# U100.net
KiCad netlist of a schematic drawn in EasyEDA Pro
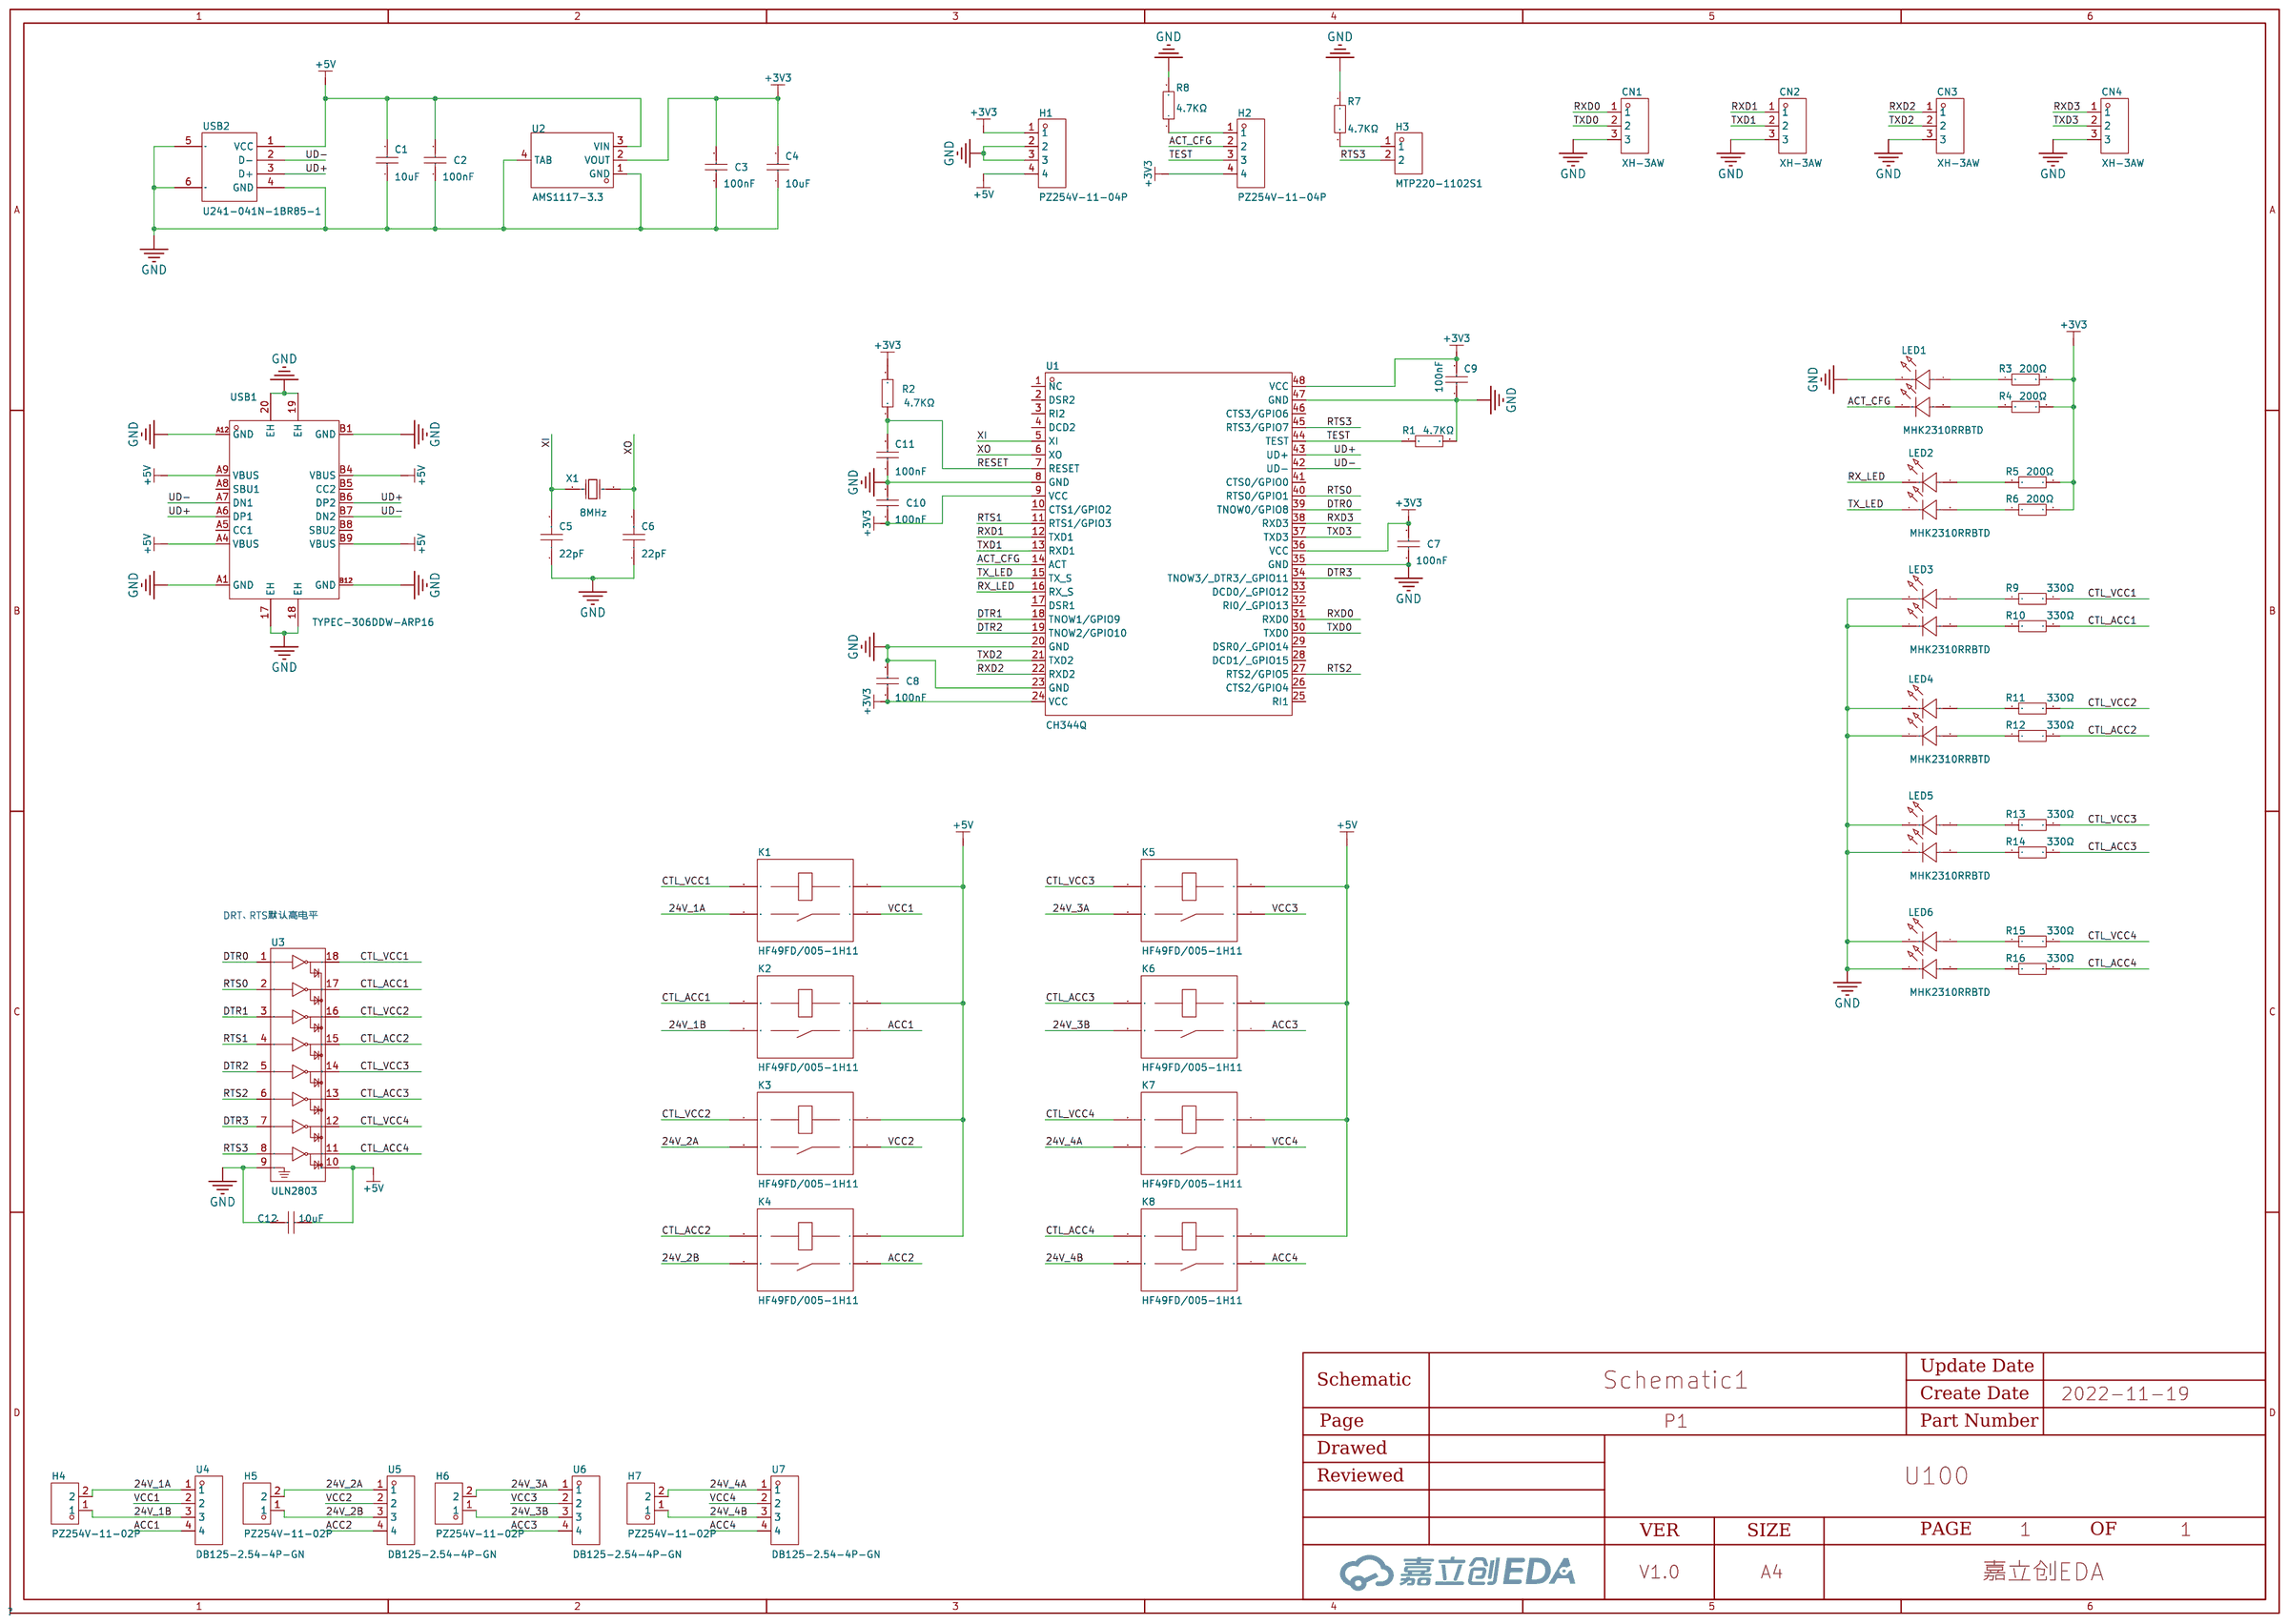
[diagram p0: schematic sheet]

(export (version "E")
  (design (tool "Eeschema 10.0.6"))
  (components
    (comp (ref "C1")
      (value "10uF")
      (footprint "easyedapro:C0805")
      (description "温度系数:X7R;容值:100nF;精度:±10%;额定电压:50V;")
      (fields (field (name "Manufacturer Part") "0805B104K500NT") (field (name "Manufacturer") "FH(风华)"))
      (libsource (lib "easyedapro") (part "0805B104K500NT"))
    )
    (comp (ref "C2")
      (value "100nF")
      (footprint "easyedapro:C0805")
      (description "温度系数:X7R;容值:100nF;精度:±10%;额定电压:50V;")
      (fields (field (name "Manufacturer Part") "0805B104K500NT") (field (name "Manufacturer") "FH(风华)"))
      (libsource (lib "easyedapro") (part "0805B104K500NT"))
    )
    (comp (ref "C3")
      (value "100nF")
      (footprint "easyedapro:C0805")
      (description "温度系数:X7R;容值:100nF;精度:±10%;额定电压:50V;")
      (fields (field (name "Manufacturer Part") "0805B104K500NT") (field (name "Manufacturer") "FH(风华)"))
      (libsource (lib "easyedapro") (part "0805B104K500NT"))
    )
    (comp (ref "C4")
      (value "10uF")
      (footprint "easyedapro:C0805")
      (description "温度系数:X7R;容值:100nF;精度:±10%;额定电压:50V;")
      (fields (field (name "Manufacturer Part") "0805B104K500NT") (field (name "Manufacturer") "FH(风华)"))
      (libsource (lib "easyedapro") (part "0805B104K500NT"))
    )
    (comp (ref "C5")
      (value "22pF")
      (footprint "easyedapro:C0805")
      (description "温度系数:C0G;精度:±5%;额定电压:50V;容值:22pF;")
      (fields (field (name "Manufacturer Part") "0805CG220J500NT") (field (name "Manufacturer") "FH(风华)"))
      (libsource (lib "easyedapro") (part "0805CG220J500NT_C24658"))
    )
    (comp (ref "C6")
      (value "22pF")
      (footprint "easyedapro:C0805")
      (description "温度系数:C0G;精度:±5%;额定电压:50V;容值:22pF;")
      (fields (field (name "Manufacturer Part") "0805CG220J500NT") (field (name "Manufacturer") "FH(风华)"))
      (libsource (lib "easyedapro") (part "0805CG220J500NT_C24658"))
    )
    (comp (ref "C7")
      (value "100nF")
      (footprint "easyedapro:C0805")
      (description "温度系数:X7R;容值:100nF;精度:±10%;额定电压:50V;")
      (fields (field (name "Manufacturer Part") "0805B104K500NT") (field (name "Manufacturer") "FH(风华)"))
      (libsource (lib "easyedapro") (part "0805B104K500NT"))
    )
    (comp (ref "C8")
      (value "100nF")
      (footprint "easyedapro:C0805")
      (description "温度系数:X7R;容值:100nF;精度:±10%;额定电压:50V;")
      (fields (field (name "Manufacturer Part") "0805B104K500NT") (field (name "Manufacturer") "FH(风华)"))
      (libsource (lib "easyedapro") (part "0805B104K500NT"))
    )
    (comp (ref "C9")
      (value "100nF")
      (footprint "easyedapro:C0805")
      (description "温度系数:X7R;容值:100nF;精度:±10%;额定电压:50V;")
      (fields (field (name "Manufacturer Part") "0805B104K500NT") (field (name "Manufacturer") "FH(风华)"))
      (libsource (lib "easyedapro") (part "0805B104K500NT"))
    )
    (comp (ref "C10")
      (value "100nF")
      (footprint "easyedapro:C0805")
      (description "温度系数:X7R;容值:100nF;精度:±10%;额定电压:50V;")
      (fields (field (name "Manufacturer Part") "0805B104K500NT") (field (name "Manufacturer") "FH(风华)"))
      (libsource (lib "easyedapro") (part "0805B104K500NT"))
    )
    (comp (ref "C11")
      (value "100nF")
      (footprint "easyedapro:C0805")
      (description "温度系数:X7R;容值:100nF;精度:±10%;额定电压:50V;")
      (fields (field (name "Manufacturer Part") "0805B104K500NT") (field (name "Manufacturer") "FH(风华)"))
      (libsource (lib "easyedapro") (part "0805B104K500NT"))
    )
    (comp (ref "C12")
      (value "10uF")
      (footprint "easyedapro:C0805")
      (description "温度系数:X7R;容值:100nF;精度:±10%;额定电压:50V;")
      (fields (field (name "Manufacturer Part") "0805B104K500NT") (field (name "Manufacturer") "FH(风华)"))
      (libsource (lib "easyedapro") (part "0805B104K500NT"))
    )
    (comp (ref "CN1")
      (value "XH-3AW")
      (footprint "easyedapro:CONN-TH_3P-P2.54_HCTL_XH-3AW")
      (description "参考系列:XH;间距:2.54mm;插针结构:1x3P;排数:1;每排PIN数:3;行距:-;公母:公型插针;安装方式:弯插;额定电流:3A;工作温度范围:-25°C~+85°C;")
      (fields (field (name "Manufacturer") "HCTL(华灿天禄)"))
      (libsource (lib "easyedapro") (part "XH-3AW_C2908612"))
    )
    (comp (ref "CN2")
      (value "XH-3AW")
      (footprint "easyedapro:CONN-TH_3P-P2.54_HCTL_XH-3AW")
      (description "参考系列:XH;间距:2.54mm;插针结构:1x3P;排数:1;每排PIN数:3;行距:-;公母:公型插针;安装方式:弯插;额定电流:3A;工作温度范围:-25°C~+85°C;")
      (fields (field (name "Manufacturer") "HCTL(华灿天禄)"))
      (libsource (lib "easyedapro") (part "XH-3AW_C2908612"))
    )
    (comp (ref "CN3")
      (value "XH-3AW")
      (footprint "easyedapro:CONN-TH_3P-P2.54_HCTL_XH-3AW")
      (description "参考系列:XH;间距:2.54mm;插针结构:1x3P;排数:1;每排PIN数:3;行距:-;公母:公型插针;安装方式:弯插;额定电流:3A;工作温度范围:-25°C~+85°C;")
      (fields (field (name "Manufacturer") "HCTL(华灿天禄)"))
      (libsource (lib "easyedapro") (part "XH-3AW_C2908612"))
    )
    (comp (ref "CN4")
      (value "XH-3AW")
      (footprint "easyedapro:CONN-TH_3P-P2.54_HCTL_XH-3AW")
      (description "参考系列:XH;间距:2.54mm;插针结构:1x3P;排数:1;每排PIN数:3;行距:-;公母:公型插针;安装方式:弯插;额定电流:3A;工作温度范围:-25°C~+85°C;")
      (fields (field (name "Manufacturer") "HCTL(华灿天禄)"))
      (libsource (lib "easyedapro") (part "XH-3AW_C2908612"))
    )
    (comp (ref "H1")
      (value "PZ254V-11-04P")
      (footprint "easyedapro:HDR-TH_4P-P2.54-V-M")
      (fields (field (name "Manufacturer") "XFCN(兴飞)"))
      (libsource (lib "easyedapro") (part "PZ254V-11-04P_C2691448"))
    )
    (comp (ref "H2")
      (value "PZ254V-11-04P")
      (footprint "easyedapro:HDR-TH_4P-P2.54-V-M")
      (fields (field (name "Manufacturer") "XFCN(兴飞)"))
      (libsource (lib "easyedapro") (part "PZ254V-11-04P_C2691448"))
    )
    (comp (ref "H3")
      (value "MTP220-1102S1")
      (footprint "easyedapro:HDR-TH_2P-P2.00-V-M")
      (fields (field (name "Manufacturer") "MINTRON(明硕)"))
      (libsource (lib "easyedapro") (part "MTP220-1102S1"))
    )
    (comp (ref "H4")
      (value "PZ254V-11-02P")
      (footprint "easyedapro:HDR-TH_2P-P2.54-V-M")
      (fields (field (name "Manufacturer") "XFCN(兴飞)"))
      (libsource (lib "easyedapro") (part "PZ254V-11-02P"))
    )
    (comp (ref "H5")
      (value "PZ254V-11-02P")
      (footprint "easyedapro:HDR-TH_2P-P2.54-V-M")
      (fields (field (name "Manufacturer") "XFCN(兴飞)"))
      (libsource (lib "easyedapro") (part "PZ254V-11-02P"))
    )
    (comp (ref "H6")
      (value "PZ254V-11-02P")
      (footprint "easyedapro:HDR-TH_2P-P2.54-V-M")
      (fields (field (name "Manufacturer") "XFCN(兴飞)"))
      (libsource (lib "easyedapro") (part "PZ254V-11-02P"))
    )
    (comp (ref "H7")
      (value "PZ254V-11-02P")
      (footprint "easyedapro:HDR-TH_2P-P2.54-V-M")
      (fields (field (name "Manufacturer") "XFCN(兴飞)"))
      (libsource (lib "easyedapro") (part "PZ254V-11-02P"))
    )
    (comp (ref "K1")
      (value "HF49FD/005-1H11")
      (footprint "easyedapro:RELAY-TH_HF49FD-XXX-1H11-XXX")
      (description "线圈电压:5V;线圈类型:非极化-单线圈;触点形式:一组常开:1A(单刀单掷-常开);最大切换电流:5A;")
      (fields (field (name "Manufacturer") "HF(宏发)"))
      (libsource (lib "easyedapro") (part "HF49FD/005-1H11"))
    )
    (comp (ref "K2")
      (value "HF49FD/005-1H11")
      (footprint "easyedapro:RELAY-TH_HF49FD-XXX-1H11-XXX")
      (description "线圈电压:5V;线圈类型:非极化-单线圈;触点形式:一组常开:1A(单刀单掷-常开);最大切换电流:5A;")
      (fields (field (name "Manufacturer") "HF(宏发)"))
      (libsource (lib "easyedapro") (part "HF49FD/005-1H11"))
    )
    (comp (ref "K3")
      (value "HF49FD/005-1H11")
      (footprint "easyedapro:RELAY-TH_HF49FD-XXX-1H11-XXX")
      (description "线圈电压:5V;线圈类型:非极化-单线圈;触点形式:一组常开:1A(单刀单掷-常开);最大切换电流:5A;")
      (fields (field (name "Manufacturer") "HF(宏发)"))
      (libsource (lib "easyedapro") (part "HF49FD/005-1H11"))
    )
    (comp (ref "K4")
      (value "HF49FD/005-1H11")
      (footprint "easyedapro:RELAY-TH_HF49FD-XXX-1H11-XXX")
      (description "线圈电压:5V;线圈类型:非极化-单线圈;触点形式:一组常开:1A(单刀单掷-常开);最大切换电流:5A;")
      (fields (field (name "Manufacturer") "HF(宏发)"))
      (libsource (lib "easyedapro") (part "HF49FD/005-1H11"))
    )
    (comp (ref "K5")
      (value "HF49FD/005-1H11")
      (footprint "easyedapro:RELAY-TH_HF49FD-XXX-1H11-XXX")
      (description "线圈电压:5V;线圈类型:非极化-单线圈;触点形式:一组常开:1A(单刀单掷-常开);最大切换电流:5A;")
      (fields (field (name "Manufacturer") "HF(宏发)"))
      (libsource (lib "easyedapro") (part "HF49FD/005-1H11"))
    )
    (comp (ref "K6")
      (value "HF49FD/005-1H11")
      (footprint "easyedapro:RELAY-TH_HF49FD-XXX-1H11-XXX")
      (description "线圈电压:5V;线圈类型:非极化-单线圈;触点形式:一组常开:1A(单刀单掷-常开);最大切换电流:5A;")
      (fields (field (name "Manufacturer") "HF(宏发)"))
      (libsource (lib "easyedapro") (part "HF49FD/005-1H11"))
    )
    (comp (ref "K7")
      (value "HF49FD/005-1H11")
      (footprint "easyedapro:RELAY-TH_HF49FD-XXX-1H11-XXX")
      (description "线圈电压:5V;线圈类型:非极化-单线圈;触点形式:一组常开:1A(单刀单掷-常开);最大切换电流:5A;")
      (fields (field (name "Manufacturer") "HF(宏发)"))
      (libsource (lib "easyedapro") (part "HF49FD/005-1H11"))
    )
    (comp (ref "K8")
      (value "HF49FD/005-1H11")
      (footprint "easyedapro:RELAY-TH_HF49FD-XXX-1H11-XXX")
      (description "线圈电压:5V;线圈类型:非极化-单线圈;触点形式:一组常开:1A(单刀单掷-常开);最大切换电流:5A;")
      (fields (field (name "Manufacturer") "HF(宏发)"))
      (libsource (lib "easyedapro") (part "HF49FD/005-1H11"))
    )
    (comp (ref "LED1")
      (value "MHK2310RRBTD")
      (footprint "easyedapro:LED-TH_4P-P2.54_MHK2310RRBTD")
      (description "发光颜色:红灯;二极管配置:-;透镜颜色:雾状红;主波长:700nm;峰值波长:-;色温:-;测试电流:20mA;功率:78mW;发光角度:80°;安装方式:-;工作温度:-25°C~+85°C;")
      (fields (field (name "Manufacturer") "MEIHUA(美华)"))
      (libsource (lib "easyedapro") (part "MHK2310RRBTD"))
    )
    (comp (ref "LED2")
      (value "MHK2310RRBTD")
      (footprint "easyedapro:LED-TH_4P-P2.54_MHK2310RRBTD")
      (description "发光颜色:红灯;二极管配置:-;透镜颜色:雾状红;主波长:700nm;峰值波长:-;色温:-;测试电流:20mA;功率:78mW;发光角度:80°;安装方式:-;工作温度:-25°C~+85°C;")
      (fields (field (name "Manufacturer") "MEIHUA(美华)"))
      (libsource (lib "easyedapro") (part "MHK2310RRBTD"))
    )
    (comp (ref "LED3")
      (value "MHK2310RRBTD")
      (footprint "easyedapro:LED-TH_4P-P2.54_MHK2310RRBTD")
      (description "发光颜色:红灯;二极管配置:-;透镜颜色:雾状红;主波长:700nm;峰值波长:-;色温:-;测试电流:20mA;功率:78mW;发光角度:80°;安装方式:-;工作温度:-25°C~+85°C;")
      (fields (field (name "Manufacturer") "MEIHUA(美华)"))
      (libsource (lib "easyedapro") (part "MHK2310RRBTD"))
    )
    (comp (ref "LED4")
      (value "MHK2310RRBTD")
      (footprint "easyedapro:LED-TH_4P-P2.54_MHK2310RRBTD")
      (description "发光颜色:红灯;二极管配置:-;透镜颜色:雾状红;主波长:700nm;峰值波长:-;色温:-;测试电流:20mA;功率:78mW;发光角度:80°;安装方式:-;工作温度:-25°C~+85°C;")
      (fields (field (name "Manufacturer") "MEIHUA(美华)"))
      (libsource (lib "easyedapro") (part "MHK2310RRBTD"))
    )
    (comp (ref "LED5")
      (value "MHK2310RRBTD")
      (footprint "easyedapro:LED-TH_4P-P2.54_MHK2310RRBTD")
      (description "发光颜色:红灯;二极管配置:-;透镜颜色:雾状红;主波长:700nm;峰值波长:-;色温:-;测试电流:20mA;功率:78mW;发光角度:80°;安装方式:-;工作温度:-25°C~+85°C;")
      (fields (field (name "Manufacturer") "MEIHUA(美华)"))
      (libsource (lib "easyedapro") (part "MHK2310RRBTD"))
    )
    (comp (ref "LED6")
      (value "MHK2310RRBTD")
      (footprint "easyedapro:LED-TH_4P-P2.54_MHK2310RRBTD")
      (description "发光颜色:红灯;二极管配置:-;透镜颜色:雾状红;主波长:700nm;峰值波长:-;色温:-;测试电流:20mA;功率:78mW;发光角度:80°;安装方式:-;工作温度:-25°C~+85°C;")
      (fields (field (name "Manufacturer") "MEIHUA(美华)"))
      (libsource (lib "easyedapro") (part "MHK2310RRBTD"))
    )
    (comp (ref "R1")
      (value "4.7KΩ")
      (footprint "easyedapro:R0805")
      (description "精度:±1%;温度系数:±800ppm/°C;阻值:0Ω;功率:0.125W;")
      (fields
        (field (name "Manufacturer Part") "0805W8F0000T5E")
        (field (name "Manufacturer") "UNI-ROYAL(厚声)")
      )
      (libsource (lib "easyedapro") (part "0805W8F0000T5E"))
    )
    (comp (ref "R2")
      (value "4.7KΩ")
      (footprint "easyedapro:R0805")
      (description "精度:±1%;温度系数:±800ppm/℃;阻值:0Ω;功率:0.125W;")
      (fields
        (field (name "Manufacturer Part") "0805W8F0000T5E")
        (field (name "Manufacturer") "UNI-ROYAL(厚声)")
      )
      (libsource (lib "easyedapro") (part "0805W8F0000T5E"))
    )
    (comp (ref "R3")
      (value "200Ω")
      (footprint "easyedapro:R0805")
      (description "精度:±1%;温度系数:±800ppm/°C;阻值:0Ω;功率:0.125W;")
      (fields
        (field (name "Manufacturer Part") "0805W8F0000T5E")
        (field (name "Manufacturer") "UNI-ROYAL(厚声)")
      )
      (libsource (lib "easyedapro") (part "0805W8F0000T5E"))
    )
    (comp (ref "R4")
      (value "200Ω")
      (footprint "easyedapro:R0805")
      (description "精度:±1%;温度系数:±800ppm/°C;阻值:0Ω;功率:0.125W;")
      (fields
        (field (name "Manufacturer Part") "0805W8F0000T5E")
        (field (name "Manufacturer") "UNI-ROYAL(厚声)")
      )
      (libsource (lib "easyedapro") (part "0805W8F0000T5E"))
    )
    (comp (ref "R5")
      (value "200Ω")
      (footprint "easyedapro:R0805")
      (description "精度:±1%;温度系数:±800ppm/°C;阻值:0Ω;功率:0.125W;")
      (fields
        (field (name "Manufacturer Part") "0805W8F0000T5E")
        (field (name "Manufacturer") "UNI-ROYAL(厚声)")
      )
      (libsource (lib "easyedapro") (part "0805W8F0000T5E"))
    )
    (comp (ref "R6")
      (value "200Ω")
      (footprint "easyedapro:R0805")
      (description "精度:±1%;温度系数:±800ppm/°C;阻值:0Ω;功率:0.125W;")
      (fields
        (field (name "Manufacturer Part") "0805W8F0000T5E")
        (field (name "Manufacturer") "UNI-ROYAL(厚声)")
      )
      (libsource (lib "easyedapro") (part "0805W8F0000T5E"))
    )
    (comp (ref "R7")
      (value "4.7KΩ")
      (footprint "easyedapro:R0805")
      (description "精度:±1%;温度系数:±800ppm/℃;阻值:0Ω;功率:0.125W;")
      (fields
        (field (name "Manufacturer Part") "0805W8F0000T5E")
        (field (name "Manufacturer") "UNI-ROYAL(厚声)")
      )
      (libsource (lib "easyedapro") (part "0805W8F0000T5E"))
    )
    (comp (ref "R8")
      (value "4.7KΩ")
      (footprint "easyedapro:R0805")
      (description "精度:±1%;温度系数:±800ppm/℃;阻值:0Ω;功率:0.125W;")
      (fields
        (field (name "Manufacturer Part") "0805W8F0000T5E")
        (field (name "Manufacturer") "UNI-ROYAL(厚声)")
      )
      (libsource (lib "easyedapro") (part "0805W8F0000T5E"))
    )
    (comp (ref "R9")
      (value "330Ω")
      (footprint "easyedapro:R0805")
      (description "精度:±1%;温度系数:±800ppm/°C;阻值:0Ω;功率:0.125W;")
      (fields
        (field (name "Manufacturer Part") "0805W8F0000T5E")
        (field (name "Manufacturer") "UNI-ROYAL(厚声)")
      )
      (libsource (lib "easyedapro") (part "0805W8F0000T5E"))
    )
    (comp (ref "R10")
      (value "330Ω")
      (footprint "easyedapro:R0805")
      (description "精度:±1%;温度系数:±800ppm/°C;阻值:0Ω;功率:0.125W;")
      (fields
        (field (name "Manufacturer Part") "0805W8F0000T5E")
        (field (name "Manufacturer") "UNI-ROYAL(厚声)")
      )
      (libsource (lib "easyedapro") (part "0805W8F0000T5E"))
    )
    (comp (ref "R11")
      (value "330Ω")
      (footprint "easyedapro:R0805")
      (description "精度:±1%;温度系数:±800ppm/°C;阻值:0Ω;功率:0.125W;")
      (fields
        (field (name "Manufacturer Part") "0805W8F0000T5E")
        (field (name "Manufacturer") "UNI-ROYAL(厚声)")
      )
      (libsource (lib "easyedapro") (part "0805W8F0000T5E"))
    )
    (comp (ref "R12")
      (value "330Ω")
      (footprint "easyedapro:R0805")
      (description "精度:±1%;温度系数:±800ppm/°C;阻值:0Ω;功率:0.125W;")
      (fields
        (field (name "Manufacturer Part") "0805W8F0000T5E")
        (field (name "Manufacturer") "UNI-ROYAL(厚声)")
      )
      (libsource (lib "easyedapro") (part "0805W8F0000T5E"))
    )
    (comp (ref "R13")
      (value "330Ω")
      (footprint "easyedapro:R0805")
      (description "精度:±1%;温度系数:±800ppm/°C;阻值:0Ω;功率:0.125W;")
      (fields
        (field (name "Manufacturer Part") "0805W8F0000T5E")
        (field (name "Manufacturer") "UNI-ROYAL(厚声)")
      )
      (libsource (lib "easyedapro") (part "0805W8F0000T5E"))
    )
    (comp (ref "R14")
      (value "330Ω")
      (footprint "easyedapro:R0805")
      (description "精度:±1%;温度系数:±800ppm/°C;阻值:0Ω;功率:0.125W;")
      (fields
        (field (name "Manufacturer Part") "0805W8F0000T5E")
        (field (name "Manufacturer") "UNI-ROYAL(厚声)")
      )
      (libsource (lib "easyedapro") (part "0805W8F0000T5E"))
    )
    (comp (ref "R15")
      (value "330Ω")
      (footprint "easyedapro:R0805")
      (description "精度:±1%;温度系数:±800ppm/°C;阻值:0Ω;功率:0.125W;")
      (fields
        (field (name "Manufacturer Part") "0805W8F0000T5E")
        (field (name "Manufacturer") "UNI-ROYAL(厚声)")
      )
      (libsource (lib "easyedapro") (part "0805W8F0000T5E"))
    )
    (comp (ref "R16")
      (value "330Ω")
      (footprint "easyedapro:R0805")
      (description "精度:±1%;温度系数:±800ppm/°C;阻值:0Ω;功率:0.125W;")
      (fields
        (field (name "Manufacturer Part") "0805W8F0000T5E")
        (field (name "Manufacturer") "UNI-ROYAL(厚声)")
      )
      (libsource (lib "easyedapro") (part "0805W8F0000T5E"))
    )
    (comp (ref "U1")
      (value "CH344Q")
      (footprint "easyedapro:LQFP-48_L7.0-W7.0-P0.50-LS9.0-BL")
      (description "USB转四路异步串口,波特率支持高达230400bps,提供4路RS485方向控制引脚,12GPIO等信号")
      (fields (field (name "Manufacturer") "WCH(南京沁恒)"))
      (libsource (lib "easyedapro") (part "CH344Q_C2988084"))
    )
    (comp (ref "U2")
      (value "AMS1117-3.3")
      (footprint "easyedapro:SOT-223-3_L6.5-W3.4-P2.30-LS7.0-BR")
      (description "输出类型:固定;输出极性:正;输出通道数:1;最大输入电压:18V;输出电压:3.3V;压差:1.4V@(1A);输出电流:800mA;电源纹波抑制比(PRSS):-;")
      (fields (field (name "Manufacturer") "PUOLOP(迪浦)"))
      (libsource (lib "easyedapro") (part "AMS1117-3.3_C351784"))
    )
    (comp (ref "U3")
      (value "ULN2803")
      (footprint "easyedapro:SOP-18_L11.5-W7.5-P1.27-LS10.3-BL")
      (fields (field (name "Manufacturer") "Gcore(扬州国芯)"))
      (libsource (lib "easyedapro") (part "ULN2803"))
    )
    (comp (ref "U4")
      (value "DB125-2.54-4P-GN")
      (footprint "easyedapro:CONN-TH_DB125-2.54-4P-GN")
      (fields (field (name "Manufacturer") "DIBO(地博电气)"))
      (libsource (lib "easyedapro") (part "DB125-2.54-4P-GN"))
    )
    (comp (ref "U5")
      (value "DB125-2.54-4P-GN")
      (footprint "easyedapro:CONN-TH_DB125-2.54-4P-GN")
      (fields (field (name "Manufacturer") "DIBO(地博电气)"))
      (libsource (lib "easyedapro") (part "DB125-2.54-4P-GN"))
    )
    (comp (ref "U6")
      (value "DB125-2.54-4P-GN")
      (footprint "easyedapro:CONN-TH_DB125-2.54-4P-GN")
      (fields (field (name "Manufacturer") "DIBO(地博电气)"))
      (libsource (lib "easyedapro") (part "DB125-2.54-4P-GN"))
    )
    (comp (ref "U7")
      (value "DB125-2.54-4P-GN")
      (footprint "easyedapro:CONN-TH_DB125-2.54-4P-GN")
      (fields (field (name "Manufacturer") "DIBO(地博电气)"))
      (libsource (lib "easyedapro") (part "DB125-2.54-4P-GN"))
    )
    (comp (ref "USB1")
      (value "TYPEC-306DDW-ARP16")
      (footprint "easyedapro:USB-C-TH_TYPEC-306DDW-ARP16")
      (fields (field (name "Manufacturer") "XUNPU(讯普)"))
      (libsource (lib "easyedapro") (part "TYPEC-306DDW-ARP16"))
    )
    (comp (ref "USB2")
      (value "U241-041N-1BR85-1")
      (footprint "easyedapro:USB-B-TH_U241-041N-1BR85-1")
      (fields (field (name "Manufacturer") "XKB Connectivity(中国星坤)"))
      (libsource (lib "easyedapro") (part "U241-041N-1BR85-1"))
    )
    (comp (ref "X1")
      (value "8MHz")
      (footprint "easyedapro:OSC-TH_L10.0-W4.5-P5.00")
      (description "晶振类型:49S晶振;频率:8MHz;频率公差:±20ppm;频率稳定度:±30ppm;负载电容:20pF;工作温度:-20℃~+70℃;")
      (fields (field (name "Manufacturer Part") "X49SD8MSD2SC") (field (name "Manufacturer") "YXC(扬兴晶振)"))
      (libsource (lib "easyedapro") (part "X49SD8MSD2SC"))
    )
  )
  (nets
    (net (code "1") (name "+3V3") (class "Default")
      (node (ref "C10") (pin "1") (pinfunction "1_1") (pintype "input"))
      (node (ref "C3") (pin "2") (pinfunction "2_2") (pintype "input"))
      (node (ref "C4") (pin "2") (pinfunction "2_2") (pintype "input"))
      (node (ref "C7") (pin "2") (pinfunction "2_2") (pintype "input"))
      (node (ref "C8") (pin "1") (pinfunction "1_1") (pintype "input"))
      (node (ref "C9") (pin "2") (pinfunction "2_2") (pintype "input"))
      (node (ref "H1") (pin "1") (pinfunction "1_1") (pintype "input"))
      (node (ref "H2") (pin "4") (pinfunction "4_4") (pintype "input"))
      (node (ref "R2") (pin "2") (pinfunction "2_2") (pintype "input"))
      (node (ref "R3") (pin "2") (pinfunction "2_2") (pintype "input"))
      (node (ref "R4") (pin "2") (pinfunction "2_2") (pintype "input"))
      (node (ref "R5") (pin "2") (pinfunction "2_2") (pintype "input"))
      (node (ref "R6") (pin "2") (pinfunction "2_2") (pintype "input"))
      (node (ref "U1") (pin "24") (pinfunction "VCC_24") (pintype "input"))
      (node (ref "U1") (pin "36") (pinfunction "VCC_36") (pintype "input"))
      (node (ref "U1") (pin "48") (pinfunction "VCC_48") (pintype "input"))
      (node (ref "U1") (pin "9") (pinfunction "VCC_9") (pintype "input"))
      (node (ref "U2") (pin "2") (pinfunction "VOUT_2") (pintype "input"))
    )
    (net (code "2") (name "+5V") (class "Default")
      (node (ref "C1") (pin "2") (pinfunction "2_2") (pintype "input"))
      (node (ref "C12") (pin "1") (pinfunction "1_1") (pintype "input"))
      (node (ref "C2") (pin "2") (pinfunction "2_2") (pintype "input"))
      (node (ref "H1") (pin "4") (pinfunction "4_4") (pintype "input"))
      (node (ref "K1") (pin "1") (pinfunction "1_1") (pintype "input"))
      (node (ref "K2") (pin "1") (pinfunction "1_1") (pintype "input"))
      (node (ref "K3") (pin "1") (pinfunction "1_1") (pintype "input"))
      (node (ref "K4") (pin "1") (pinfunction "1_1") (pintype "input"))
      (node (ref "K5") (pin "1") (pinfunction "1_1") (pintype "input"))
      (node (ref "K6") (pin "1") (pinfunction "1_1") (pintype "input"))
      (node (ref "K7") (pin "1") (pinfunction "1_1") (pintype "input"))
      (node (ref "K8") (pin "1") (pinfunction "1_1") (pintype "input"))
      (node (ref "U2") (pin "3") (pinfunction "VIN_3") (pintype "input"))
      (node (ref "U3") (pin "10") (pinfunction "COMMON_10") (pintype "input"))
      (node (ref "USB1") (pin "A4") (pinfunction "VBUS_A4") (pintype "input"))
      (node (ref "USB1") (pin "A9") (pinfunction "VBUS_A9") (pintype "input"))
      (node (ref "USB1") (pin "B4") (pinfunction "VBUS_B4") (pintype "input"))
      (node (ref "USB1") (pin "B9") (pinfunction "VBUS_B9") (pintype "input"))
      (node (ref "USB2") (pin "1") (pinfunction "VCC_1") (pintype "input"))
    )
    (net (code "3") (name "/24V_1A") (class "Default")
      (node (ref "H4") (pin "2") (pinfunction "2_2") (pintype "input"))
      (node (ref "K1") (pin "3") (pinfunction "3_3") (pintype "input"))
      (node (ref "U4") (pin "1") (pinfunction "1_1") (pintype "input"))
    )
    (net (code "4") (name "/24V_1B") (class "Default")
      (node (ref "H4") (pin "1") (pinfunction "1_1") (pintype "input"))
      (node (ref "K2") (pin "3") (pinfunction "3_3") (pintype "input"))
      (node (ref "U4") (pin "3") (pinfunction "3_3") (pintype "input"))
    )
    (net (code "5") (name "/24V_2A") (class "Default")
      (node (ref "H5") (pin "2") (pinfunction "2_2") (pintype "input"))
      (node (ref "K3") (pin "3") (pinfunction "3_3") (pintype "input"))
      (node (ref "U5") (pin "1") (pinfunction "1_1") (pintype "input"))
    )
    (net (code "6") (name "/24V_2B") (class "Default")
      (node (ref "H5") (pin "1") (pinfunction "1_1") (pintype "input"))
      (node (ref "K4") (pin "3") (pinfunction "3_3") (pintype "input"))
      (node (ref "U5") (pin "3") (pinfunction "3_3") (pintype "input"))
    )
    (net (code "7") (name "/24V_3A") (class "Default")
      (node (ref "H6") (pin "2") (pinfunction "2_2") (pintype "input"))
      (node (ref "K5") (pin "3") (pinfunction "3_3") (pintype "input"))
      (node (ref "U6") (pin "1") (pinfunction "1_1") (pintype "input"))
    )
    (net (code "8") (name "/24V_3B") (class "Default")
      (node (ref "H6") (pin "1") (pinfunction "1_1") (pintype "input"))
      (node (ref "K6") (pin "3") (pinfunction "3_3") (pintype "input"))
      (node (ref "U6") (pin "3") (pinfunction "3_3") (pintype "input"))
    )
    (net (code "9") (name "/24V_4A") (class "Default")
      (node (ref "H7") (pin "2") (pinfunction "2_2") (pintype "input"))
      (node (ref "K7") (pin "3") (pinfunction "3_3") (pintype "input"))
      (node (ref "U7") (pin "1") (pinfunction "1_1") (pintype "input"))
    )
    (net (code "10") (name "/24V_4B") (class "Default")
      (node (ref "H7") (pin "1") (pinfunction "1_1") (pintype "input"))
      (node (ref "K8") (pin "3") (pinfunction "3_3") (pintype "input"))
      (node (ref "U7") (pin "3") (pinfunction "3_3") (pintype "input"))
    )
    (net (code "11") (name "/ACC1") (class "Default")
      (node (ref "K2") (pin "4") (pinfunction "4_4") (pintype "input"))
      (node (ref "U4") (pin "4") (pinfunction "4_4") (pintype "input"))
    )
    (net (code "12") (name "/ACC2") (class "Default")
      (node (ref "K4") (pin "4") (pinfunction "4_4") (pintype "input"))
      (node (ref "U5") (pin "4") (pinfunction "4_4") (pintype "input"))
    )
    (net (code "13") (name "/ACC3") (class "Default")
      (node (ref "K6") (pin "4") (pinfunction "4_4") (pintype "input"))
      (node (ref "U6") (pin "4") (pinfunction "4_4") (pintype "input"))
    )
    (net (code "14") (name "/ACC4") (class "Default")
      (node (ref "K8") (pin "4") (pinfunction "4_4") (pintype "input"))
      (node (ref "U7") (pin "4") (pinfunction "4_4") (pintype "input"))
    )
    (net (code "15") (name "/ACT_CFG") (class "Default")
      (node (ref "H2") (pin "2") (pinfunction "2_2") (pintype "input"))
      (node (ref "LED1") (pin "1") (pinfunction "K_1") (pintype "input"))
      (node (ref "U1") (pin "14") (pinfunction "ACT_14") (pintype "input"))
    )
    (net (code "16") (name "/CTL_ACC1") (class "Default")
      (node (ref "K2") (pin "2") (pinfunction "2_2") (pintype "input"))
      (node (ref "R10") (pin "2") (pinfunction "2_2") (pintype "input"))
      (node (ref "U3") (pin "17") (pinfunction "O2_17") (pintype "input"))
    )
    (net (code "17") (name "/CTL_ACC2") (class "Default")
      (node (ref "K4") (pin "2") (pinfunction "2_2") (pintype "input"))
      (node (ref "R12") (pin "2") (pinfunction "2_2") (pintype "input"))
      (node (ref "U3") (pin "15") (pinfunction "O4_15") (pintype "input"))
    )
    (net (code "18") (name "/CTL_ACC3") (class "Default")
      (node (ref "K6") (pin "2") (pinfunction "2_2") (pintype "input"))
      (node (ref "R14") (pin "2") (pinfunction "2_2") (pintype "input"))
      (node (ref "U3") (pin "13") (pinfunction "O6_13") (pintype "input"))
    )
    (net (code "19") (name "/CTL_ACC4") (class "Default")
      (node (ref "K8") (pin "2") (pinfunction "2_2") (pintype "input"))
      (node (ref "R16") (pin "2") (pinfunction "2_2") (pintype "input"))
      (node (ref "U3") (pin "11") (pinfunction "O8_11") (pintype "input"))
    )
    (net (code "20") (name "/CTL_VCC1") (class "Default")
      (node (ref "K1") (pin "2") (pinfunction "2_2") (pintype "input"))
      (node (ref "R9") (pin "2") (pinfunction "2_2") (pintype "input"))
      (node (ref "U3") (pin "18") (pinfunction "O1_18") (pintype "input"))
    )
    (net (code "21") (name "/CTL_VCC2") (class "Default")
      (node (ref "K3") (pin "2") (pinfunction "2_2") (pintype "input"))
      (node (ref "R11") (pin "2") (pinfunction "2_2") (pintype "input"))
      (node (ref "U3") (pin "16") (pinfunction "O3_16") (pintype "input"))
    )
    (net (code "22") (name "/CTL_VCC3") (class "Default")
      (node (ref "K5") (pin "2") (pinfunction "2_2") (pintype "input"))
      (node (ref "R13") (pin "2") (pinfunction "2_2") (pintype "input"))
      (node (ref "U3") (pin "14") (pinfunction "O5_14") (pintype "input"))
    )
    (net (code "23") (name "/CTL_VCC4") (class "Default")
      (node (ref "K7") (pin "2") (pinfunction "2_2") (pintype "input"))
      (node (ref "R15") (pin "2") (pinfunction "2_2") (pintype "input"))
      (node (ref "U3") (pin "12") (pinfunction "O7_12") (pintype "input"))
    )
    (net (code "24") (name "/DTR0") (class "Default")
      (node (ref "U1") (pin "39") (pinfunction "TNOW0/GPIO8_39") (pintype "input"))
      (node (ref "U3") (pin "1") (pinfunction "I1_1") (pintype "input"))
    )
    (net (code "25") (name "/DTR1") (class "Default")
      (node (ref "U1") (pin "18") (pinfunction "TNOW1/GPIO9_18") (pintype "input"))
      (node (ref "U3") (pin "3") (pinfunction "I3_3") (pintype "input"))
    )
    (net (code "26") (name "/DTR2") (class "Default")
      (node (ref "U1") (pin "19") (pinfunction "TNOW2/GPIO10_19") (pintype "input"))
      (node (ref "U3") (pin "5") (pinfunction "I5_5") (pintype "input"))
    )
    (net (code "27") (name "/DTR3") (class "Default")
      (node (ref "U1") (pin "34") (pinfunction "TNOW3/_DTR3/_GPIO11_34") (pintype "input"))
      (node (ref "U3") (pin "7") (pinfunction "I7_7") (pintype "input"))
    )
    (net (code "28") (name "/RESET") (class "Default")
      (node (ref "C11") (pin "2") (pinfunction "2_2") (pintype "input"))
      (node (ref "R2") (pin "1") (pinfunction "1_1") (pintype "input"))
      (node (ref "U1") (pin "7") (pinfunction "RESET_7") (pintype "input"))
    )
    (net (code "29") (name "/RTS0") (class "Default")
      (node (ref "U1") (pin "40") (pinfunction "RTS0/GPIO1_40") (pintype "input"))
      (node (ref "U3") (pin "2") (pinfunction "I2_2") (pintype "input"))
    )
    (net (code "30") (name "/RTS1") (class "Default")
      (node (ref "U1") (pin "11") (pinfunction "RTS1/GPIO3_11") (pintype "input"))
      (node (ref "U3") (pin "4") (pinfunction "I4_4") (pintype "input"))
    )
    (net (code "31") (name "/RTS2") (class "Default")
      (node (ref "U1") (pin "27") (pinfunction "RTS2/GPIO5_27") (pintype "input"))
      (node (ref "U3") (pin "6") (pinfunction "I6_6") (pintype "input"))
    )
    (net (code "32") (name "/RTS3") (class "Default")
      (node (ref "H3") (pin "2") (pinfunction "2_2") (pintype "input"))
      (node (ref "U1") (pin "45") (pinfunction "RTS3/GPIO7_45") (pintype "input"))
      (node (ref "U3") (pin "8") (pinfunction "I8_8") (pintype "input"))
    )
    (net (code "33") (name "/RXD0") (class "Default")
      (node (ref "CN1") (pin "1") (pinfunction "1_1") (pintype "input"))
      (node (ref "U1") (pin "31") (pinfunction "RXD0_31") (pintype "input"))
    )
    (net (code "34") (name "/RXD1") (class "Default")
      (node (ref "CN2") (pin "1") (pinfunction "1_1") (pintype "input"))
      (node (ref "U1") (pin "12") (pinfunction "TXD1_12") (pintype "input"))
    )
    (net (code "35") (name "/RXD2") (class "Default")
      (node (ref "CN3") (pin "1") (pinfunction "1_1") (pintype "input"))
      (node (ref "U1") (pin "22") (pinfunction "RXD2_22") (pintype "input"))
    )
    (net (code "36") (name "/RXD3") (class "Default")
      (node (ref "CN4") (pin "1") (pinfunction "1_1") (pintype "input"))
      (node (ref "U1") (pin "38") (pinfunction "RXD3_38") (pintype "input"))
    )
    (net (code "37") (name "/RX_LED") (class "Default")
      (node (ref "LED2") (pin "3") (pinfunction "K_3") (pintype "input"))
      (node (ref "U1") (pin "16") (pinfunction "RX_S_16") (pintype "input"))
    )
    (net (code "38") (name "/TEST") (class "Default")
      (node (ref "H2") (pin "3") (pinfunction "3_3") (pintype "input"))
      (node (ref "R1") (pin "1") (pinfunction "1_1") (pintype "input"))
      (node (ref "U1") (pin "44") (pinfunction "TEST_44") (pintype "input"))
    )
    (net (code "39") (name "/TXD0") (class "Default")
      (node (ref "CN1") (pin "2") (pinfunction "2_2") (pintype "input"))
      (node (ref "U1") (pin "30") (pinfunction "TXD0_30") (pintype "input"))
    )
    (net (code "40") (name "/TXD1") (class "Default")
      (node (ref "CN2") (pin "2") (pinfunction "2_2") (pintype "input"))
      (node (ref "U1") (pin "13") (pinfunction "RXD1_13") (pintype "input"))
    )
    (net (code "41") (name "/TXD2") (class "Default")
      (node (ref "CN3") (pin "2") (pinfunction "2_2") (pintype "input"))
      (node (ref "U1") (pin "21") (pinfunction "TXD2_21") (pintype "input"))
    )
    (net (code "42") (name "/TXD3") (class "Default")
      (node (ref "CN4") (pin "2") (pinfunction "2_2") (pintype "input"))
      (node (ref "U1") (pin "37") (pinfunction "TXD3_37") (pintype "input"))
    )
    (net (code "43") (name "/TX_LED") (class "Default")
      (node (ref "LED2") (pin "1") (pinfunction "K_1") (pintype "input"))
      (node (ref "U1") (pin "15") (pinfunction "TX_S_15") (pintype "input"))
    )
    (net (code "44") (name "/UD+") (class "Default")
      (node (ref "U1") (pin "43") (pinfunction "UD+_43") (pintype "input"))
      (node (ref "USB1") (pin "A6") (pinfunction "DP1_A6") (pintype "input"))
      (node (ref "USB1") (pin "B6") (pinfunction "DP2_B6") (pintype "input"))
      (node (ref "USB2") (pin "3") (pinfunction "D+_3") (pintype "input"))
    )
    (net (code "45") (name "/UD-") (class "Default")
      (node (ref "U1") (pin "42") (pinfunction "UD-_42") (pintype "input"))
      (node (ref "USB1") (pin "A7") (pinfunction "DN1_A7") (pintype "input"))
      (node (ref "USB1") (pin "B7") (pinfunction "DN2_B7") (pintype "input"))
      (node (ref "USB2") (pin "2") (pinfunction "D-_2") (pintype "input"))
    )
    (net (code "46") (name "/VCC1") (class "Default")
      (node (ref "K1") (pin "4") (pinfunction "4_4") (pintype "input"))
      (node (ref "U4") (pin "2") (pinfunction "2_2") (pintype "input"))
    )
    (net (code "47") (name "/VCC2") (class "Default")
      (node (ref "K3") (pin "4") (pinfunction "4_4") (pintype "input"))
      (node (ref "U5") (pin "2") (pinfunction "2_2") (pintype "input"))
    )
    (net (code "48") (name "/VCC3") (class "Default")
      (node (ref "K5") (pin "4") (pinfunction "4_4") (pintype "input"))
      (node (ref "U6") (pin "2") (pinfunction "2_2") (pintype "input"))
    )
    (net (code "49") (name "/VCC4") (class "Default")
      (node (ref "K7") (pin "4") (pinfunction "4_4") (pintype "input"))
      (node (ref "U7") (pin "2") (pinfunction "2_2") (pintype "input"))
    )
    (net (code "50") (name "/XI") (class "Default")
      (node (ref "C5") (pin "2") (pinfunction "2_2") (pintype "input"))
      (node (ref "U1") (pin "5") (pinfunction "XI_5") (pintype "input"))
      (node (ref "X1") (pin "1") (pinfunction "OSC1_1") (pintype "input"))
    )
    (net (code "51") (name "/XO") (class "Default")
      (node (ref "C6") (pin "2") (pinfunction "2_2") (pintype "input"))
      (node (ref "U1") (pin "6") (pinfunction "XO_6") (pintype "input"))
      (node (ref "X1") (pin "2") (pinfunction "OSC2_2") (pintype "input"))
    )
    (net (code "52") (name "GND") (class "Default")
      (node (ref "C1") (pin "1") (pinfunction "1_1") (pintype "input"))
      (node (ref "C10") (pin "2") (pinfunction "2_2") (pintype "input"))
      (node (ref "C11") (pin "1") (pinfunction "1_1") (pintype "input"))
      (node (ref "C12") (pin "2") (pinfunction "2_2") (pintype "input"))
      (node (ref "C2") (pin "1") (pinfunction "1_1") (pintype "input"))
      (node (ref "C3") (pin "1") (pinfunction "1_1") (pintype "input"))
      (node (ref "C4") (pin "1") (pinfunction "1_1") (pintype "input"))
      (node (ref "C5") (pin "1") (pinfunction "1_1") (pintype "input"))
      (node (ref "C6") (pin "1") (pinfunction "1_1") (pintype "input"))
      (node (ref "C7") (pin "1") (pinfunction "1_1") (pintype "input"))
      (node (ref "C8") (pin "2") (pinfunction "2_2") (pintype "input"))
      (node (ref "C9") (pin "1") (pinfunction "1_1") (pintype "input"))
      (node (ref "CN1") (pin "3") (pinfunction "3_3") (pintype "input"))
      (node (ref "CN2") (pin "3") (pinfunction "3_3") (pintype "input"))
      (node (ref "CN3") (pin "3") (pinfunction "3_3") (pintype "input"))
      (node (ref "CN4") (pin "3") (pinfunction "3_3") (pintype "input"))
      (node (ref "H1") (pin "2") (pinfunction "2_2") (pintype "input"))
      (node (ref "H1") (pin "3") (pinfunction "3_3") (pintype "input"))
      (node (ref "LED1") (pin "3") (pinfunction "K_3") (pintype "input"))
      (node (ref "LED3") (pin "1") (pinfunction "K_1") (pintype "input"))
      (node (ref "LED3") (pin "3") (pinfunction "K_3") (pintype "input"))
      (node (ref "LED4") (pin "1") (pinfunction "K_1") (pintype "input"))
      (node (ref "LED4") (pin "3") (pinfunction "K_3") (pintype "input"))
      (node (ref "LED5") (pin "1") (pinfunction "K_1") (pintype "input"))
      (node (ref "LED5") (pin "3") (pinfunction "K_3") (pintype "input"))
      (node (ref "LED6") (pin "1") (pinfunction "K_1") (pintype "input"))
      (node (ref "LED6") (pin "3") (pinfunction "K_3") (pintype "input"))
      (node (ref "R1") (pin "2") (pinfunction "2_2") (pintype "input"))
      (node (ref "R7") (pin "1") (pinfunction "1_1") (pintype "input"))
      (node (ref "R8") (pin "2") (pinfunction "2_2") (pintype "input"))
      (node (ref "U1") (pin "20") (pinfunction "GND_20") (pintype "input"))
      (node (ref "U1") (pin "23") (pinfunction "GND_23") (pintype "input"))
      (node (ref "U1") (pin "35") (pinfunction "GND_35") (pintype "input"))
      (node (ref "U1") (pin "47") (pinfunction "GND_47") (pintype "input"))
      (node (ref "U1") (pin "8") (pinfunction "GND_8") (pintype "input"))
      (node (ref "U2") (pin "1") (pinfunction "GND_1") (pintype "input"))
      (node (ref "U2") (pin "4") (pinfunction "TAB_4") (pintype "input"))
      (node (ref "U3") (pin "9") (pinfunction "GND_9") (pintype "input"))
      (node (ref "USB1") (pin "17") (pinfunction "EH_17") (pintype "input"))
      (node (ref "USB1") (pin "18") (pinfunction "EH_18") (pintype "input"))
      (node (ref "USB1") (pin "19") (pinfunction "EH_19") (pintype "input"))
      (node (ref "USB1") (pin "20") (pinfunction "EH_20") (pintype "input"))
      (node (ref "USB1") (pin "A1") (pinfunction "GND_A1") (pintype "input"))
      (node (ref "USB1") (pin "A12") (pinfunction "GND_A12") (pintype "input"))
      (node (ref "USB1") (pin "B1") (pinfunction "GND_B1") (pintype "input"))
      (node (ref "USB1") (pin "B12") (pinfunction "GND_B12") (pintype "input"))
      (node (ref "USB2") (pin "4") (pinfunction "GND_4") (pintype "input"))
      (node (ref "USB2") (pin "5") (pinfunction "SH1_5") (pintype "input"))
      (node (ref "USB2") (pin "6") (pinfunction "SH2_6") (pintype "input"))
    )
    (net (code "53") (name "Net-(H2-Pad1)") (class "Default")
      (node (ref "H2") (pin "1") (pinfunction "1_1") (pintype "input"))
      (node (ref "R8") (pin "1") (pinfunction "1_1") (pintype "input"))
    )
    (net (code "54") (name "Net-(H3-Pad1)") (class "Default")
      (node (ref "H3") (pin "1") (pinfunction "1_1") (pintype "input"))
      (node (ref "R7") (pin "2") (pinfunction "2_2") (pintype "input"))
    )
    (net (code "55") (name "Net-(LED1-A-Pad2)") (class "Default")
      (node (ref "LED1") (pin "2") (pinfunction "A_2") (pintype "input"))
      (node (ref "R4") (pin "1") (pinfunction "1_1") (pintype "input"))
    )
    (net (code "56") (name "Net-(LED1-A-Pad4)") (class "Default")
      (node (ref "LED1") (pin "4") (pinfunction "A_4") (pintype "input"))
      (node (ref "R3") (pin "1") (pinfunction "1_1") (pintype "input"))
    )
    (net (code "57") (name "Net-(LED2-A-Pad2)") (class "Default")
      (node (ref "LED2") (pin "2") (pinfunction "A_2") (pintype "input"))
      (node (ref "R6") (pin "1") (pinfunction "1_1") (pintype "input"))
    )
    (net (code "58") (name "Net-(LED2-A-Pad4)") (class "Default")
      (node (ref "LED2") (pin "4") (pinfunction "A_4") (pintype "input"))
      (node (ref "R5") (pin "1") (pinfunction "1_1") (pintype "input"))
    )
    (net (code "59") (name "Net-(LED3-A-Pad2)") (class "Default")
      (node (ref "LED3") (pin "2") (pinfunction "A_2") (pintype "input"))
      (node (ref "R10") (pin "1") (pinfunction "1_1") (pintype "input"))
    )
    (net (code "60") (name "Net-(LED3-A-Pad4)") (class "Default")
      (node (ref "LED3") (pin "4") (pinfunction "A_4") (pintype "input"))
      (node (ref "R9") (pin "1") (pinfunction "1_1") (pintype "input"))
    )
    (net (code "61") (name "Net-(LED4-A-Pad2)") (class "Default")
      (node (ref "LED4") (pin "2") (pinfunction "A_2") (pintype "input"))
      (node (ref "R12") (pin "1") (pinfunction "1_1") (pintype "input"))
    )
    (net (code "62") (name "Net-(LED4-A-Pad4)") (class "Default")
      (node (ref "LED4") (pin "4") (pinfunction "A_4") (pintype "input"))
      (node (ref "R11") (pin "1") (pinfunction "1_1") (pintype "input"))
    )
    (net (code "63") (name "Net-(LED5-A-Pad2)") (class "Default")
      (node (ref "LED5") (pin "2") (pinfunction "A_2") (pintype "input"))
      (node (ref "R14") (pin "1") (pinfunction "1_1") (pintype "input"))
    )
    (net (code "64") (name "Net-(LED5-A-Pad4)") (class "Default")
      (node (ref "LED5") (pin "4") (pinfunction "A_4") (pintype "input"))
      (node (ref "R13") (pin "1") (pinfunction "1_1") (pintype "input"))
    )
    (net (code "65") (name "Net-(LED6-A-Pad2)") (class "Default")
      (node (ref "LED6") (pin "2") (pinfunction "A_2") (pintype "input"))
      (node (ref "R16") (pin "1") (pinfunction "1_1") (pintype "input"))
    )
    (net (code "66") (name "Net-(LED6-A-Pad4)") (class "Default")
      (node (ref "LED6") (pin "4") (pinfunction "A_4") (pintype "input"))
      (node (ref "R15") (pin "1") (pinfunction "1_1") (pintype "input"))
    )
    (net (code "67") (name "unconnected-(U1-CTS0{slash}GPIO0-Pad41)") (class "Default")
      (node (ref "U1") (pin "41") (pinfunction "CTS0/GPIO0_41") (pintype "input"))
    )
    (net (code "68") (name "unconnected-(U1-CTS1{slash}GPIO2-Pad10)") (class "Default")
      (node (ref "U1") (pin "10") (pinfunction "CTS1/GPIO2_10") (pintype "input"))
    )
    (net (code "69") (name "unconnected-(U1-CTS2{slash}GPIO4-Pad26)") (class "Default")
      (node (ref "U1") (pin "26") (pinfunction "CTS2/GPIO4_26") (pintype "input"))
    )
    (net (code "70") (name "unconnected-(U1-CTS3{slash}GPIO6-Pad46)") (class "Default")
      (node (ref "U1") (pin "46") (pinfunction "CTS3/GPIO6_46") (pintype "input"))
    )
    (net (code "71") (name "unconnected-(U1-DCD0{slash}_GPIO12-Pad33)") (class "Default")
      (node (ref "U1") (pin "33") (pinfunction "DCD0/_GPIO12_33") (pintype "input"))
    )
    (net (code "72") (name "unconnected-(U1-DCD1{slash}_GPIO15-Pad28)") (class "Default")
      (node (ref "U1") (pin "28") (pinfunction "DCD1/_GPIO15_28") (pintype "input"))
    )
    (net (code "73") (name "unconnected-(U1-DCD2-Pad4)") (class "Default")
      (node (ref "U1") (pin "4") (pinfunction "DCD2_4") (pintype "input"))
    )
    (net (code "74") (name "unconnected-(U1-DSR0{slash}_GPIO14-Pad29)") (class "Default")
      (node (ref "U1") (pin "29") (pinfunction "DSR0/_GPIO14_29") (pintype "input"))
    )
    (net (code "75") (name "unconnected-(U1-DSR1-Pad17)") (class "Default")
      (node (ref "U1") (pin "17") (pinfunction "DSR1_17") (pintype "input"))
    )
    (net (code "76") (name "unconnected-(U1-DSR2-Pad2)") (class "Default")
      (node (ref "U1") (pin "2") (pinfunction "DSR2_2") (pintype "input"))
    )
    (net (code "77") (name "unconnected-(U1-NC-Pad1)") (class "Default")
      (node (ref "U1") (pin "1") (pinfunction "NC_1") (pintype "input"))
    )
    (net (code "78") (name "unconnected-(U1-RI0{slash}_GPIO13-Pad32)") (class "Default")
      (node (ref "U1") (pin "32") (pinfunction "RI0/_GPIO13_32") (pintype "input"))
    )
    (net (code "79") (name "unconnected-(U1-RI1-Pad25)") (class "Default")
      (node (ref "U1") (pin "25") (pinfunction "RI1_25") (pintype "input"))
    )
    (net (code "80") (name "unconnected-(U1-RI2-Pad3)") (class "Default")
      (node (ref "U1") (pin "3") (pinfunction "RI2_3") (pintype "input"))
    )
    (net (code "81") (name "unconnected-(USB1-CC1-PadA5)") (class "Default")
      (node (ref "USB1") (pin "A5") (pinfunction "CC1_A5") (pintype "input"))
    )
    (net (code "82") (name "unconnected-(USB1-CC2-PadB5)") (class "Default")
      (node (ref "USB1") (pin "B5") (pinfunction "CC2_B5") (pintype "input"))
    )
    (net (code "83") (name "unconnected-(USB1-SBU1-PadA8)") (class "Default")
      (node (ref "USB1") (pin "A8") (pinfunction "SBU1_A8") (pintype "input"))
    )
    (net (code "84") (name "unconnected-(USB1-SBU2-PadB8)") (class "Default")
      (node (ref "USB1") (pin "B8") (pinfunction "SBU2_B8") (pintype "input"))
    )
  )
)
